# 1-Schematic_task10_1_PCB.net
KiCad netlist of a schematic drawn in EasyEDA
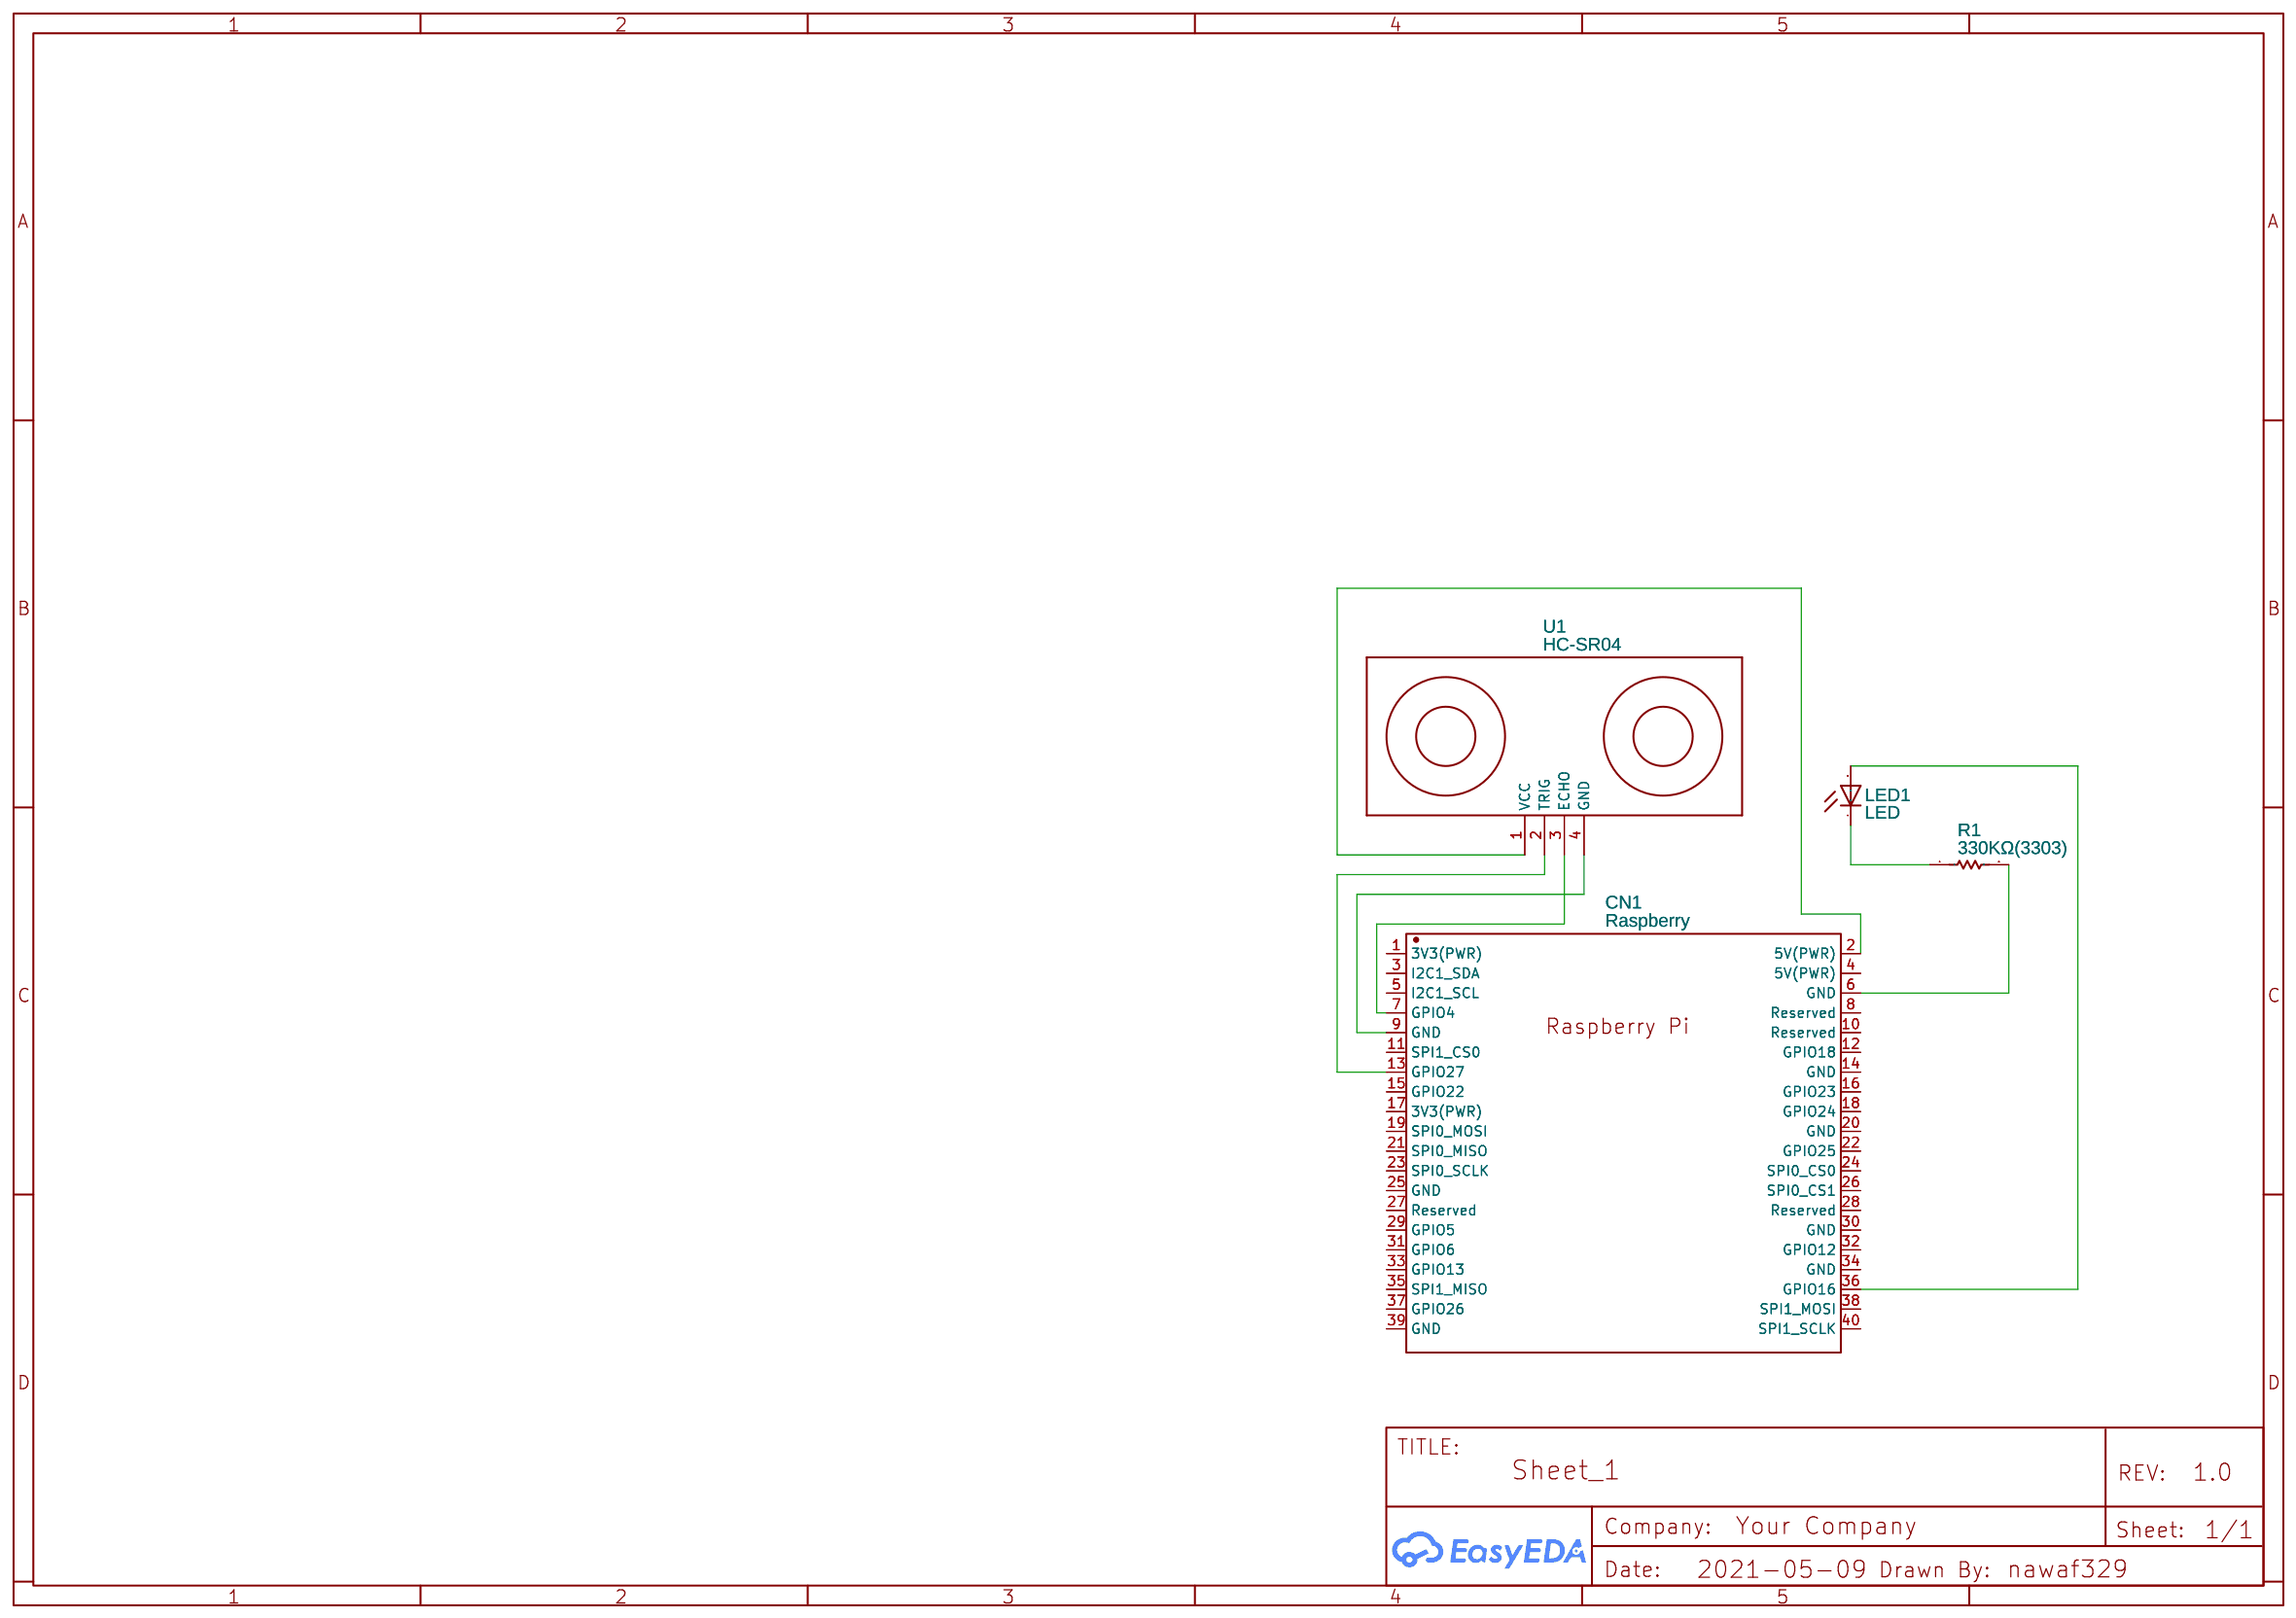
[diagram p0: schematic sheet]

(export (version "E")
  (design (tool "Eeschema 10.0.6"))
  (components
    (comp (ref "CN1") (value "Raspberry") (libsource (lib "") (part "Raspberry Pi 2")))
    (comp (ref "LED1") (value "LED") (libsource (lib "") (part "LED")))
    (comp (ref "R1")
      (value "330KΩ(3303)")
      (fields (field (name "BOM_Manufacturer Part") "RALEC") (field (name "BOM_Supplier Part") "undefined"))
      (libsource (lib "") (part "330KΩ(3303)"))
    )
    (comp (ref "U1") (value "HC-SR04") (libsource (lib "") (part "HC-SR04")))
  )
  (nets
    (net (code "1") (name "Net-(CN1-GND-Pad6)") (class "Default")
      (node (ref "CN1") (pin "6") (pinfunction "GND_6") (pintype "passive"))
      (node (ref "R1") (pin "2") (pinfunction "2_2") (pintype "unspecified"))
    )
    (net (code "2") (name "Net-(CN1-GPIO4)") (class "Default")
      (node (ref "CN1") (pin "7") (pinfunction "GPIO4_7") (pintype "bidirectional"))
      (node (ref "U1") (pin "3") (pinfunction "ECHO_3") (pintype "output"))
    )
    (net (code "3") (name "Net-(CN1-GPIO16)") (class "Default")
      (node (ref "CN1") (pin "36") (pinfunction "GPIO16_36") (pintype "bidirectional"))
      (node (ref "LED1") (pin "A") (pinfunction "A_A") (pintype "unspecified"))
    )
    (net (code "4") (name "Net-(CN1-GPIO27)") (class "Default")
      (node (ref "CN1") (pin "13") (pinfunction "GPIO27_13") (pintype "bidirectional"))
      (node (ref "U1") (pin "2") (pinfunction "TRIG_2") (pintype "input"))
    )
    (net (code "5") (name "Net-(LED1-C)") (class "Default")
      (node (ref "LED1") (pin "K") (pinfunction "C_K") (pintype "unspecified"))
      (node (ref "R1") (pin "1") (pinfunction "1_1") (pintype "unspecified"))
    )
    (net (code "6") (name "Net-(U1-GND)") (class "Default")
      (node (ref "CN1") (pin "9") (pinfunction "GND_9") (pintype "passive"))
      (node (ref "U1") (pin "4") (pinfunction "GND_4") (pintype "passive"))
    )
    (net (code "7") (name "Net-(U1-VCC)") (class "Default")
      (node (ref "CN1") (pin "2") (pinfunction "5V(PWR)_2") (pintype "passive"))
      (node (ref "U1") (pin "1") (pinfunction "VCC_1") (pintype "passive"))
    )
    (net (code "8") (name "unconnected-(CN1-3V3(PWR)-Pad1)") (class "Default")
      (node (ref "CN1") (pin "1") (pinfunction "3V3(PWR)_1") (pintype "passive"))
    )
    (net (code "9") (name "unconnected-(CN1-3V3(PWR)-Pad17)") (class "Default")
      (node (ref "CN1") (pin "17") (pinfunction "3V3(PWR)_17") (pintype "passive"))
    )
    (net (code "10") (name "unconnected-(CN1-5V(PWR)-Pad4)") (class "Default")
      (node (ref "CN1") (pin "4") (pinfunction "5V(PWR)_4") (pintype "passive"))
    )
    (net (code "11") (name "unconnected-(CN1-GND-Pad14)") (class "Default")
      (node (ref "CN1") (pin "14") (pinfunction "GND_14") (pintype "passive"))
    )
    (net (code "12") (name "unconnected-(CN1-GND-Pad20)") (class "Default")
      (node (ref "CN1") (pin "20") (pinfunction "GND_20") (pintype "passive"))
    )
    (net (code "13") (name "unconnected-(CN1-GND-Pad25)") (class "Default")
      (node (ref "CN1") (pin "25") (pinfunction "GND_25") (pintype "passive"))
    )
    (net (code "14") (name "unconnected-(CN1-GND-Pad30)") (class "Default")
      (node (ref "CN1") (pin "30") (pinfunction "GND_30") (pintype "passive"))
    )
    (net (code "15") (name "unconnected-(CN1-GND-Pad34)") (class "Default")
      (node (ref "CN1") (pin "34") (pinfunction "GND_34") (pintype "passive"))
    )
    (net (code "16") (name "unconnected-(CN1-GND-Pad39)") (class "Default")
      (node (ref "CN1") (pin "39") (pinfunction "GND_39") (pintype "passive"))
    )
    (net (code "17") (name "unconnected-(CN1-GPIO5-Pad29)") (class "Default")
      (node (ref "CN1") (pin "29") (pinfunction "GPIO5_29") (pintype "bidirectional"))
    )
    (net (code "18") (name "unconnected-(CN1-GPIO6-Pad31)") (class "Default")
      (node (ref "CN1") (pin "31") (pinfunction "GPIO6_31") (pintype "bidirectional"))
    )
    (net (code "19") (name "unconnected-(CN1-GPIO12-Pad32)") (class "Default")
      (node (ref "CN1") (pin "32") (pinfunction "GPIO12_32") (pintype "bidirectional"))
    )
    (net (code "20") (name "unconnected-(CN1-GPIO13-Pad33)") (class "Default")
      (node (ref "CN1") (pin "33") (pinfunction "GPIO13_33") (pintype "bidirectional"))
    )
    (net (code "21") (name "unconnected-(CN1-GPIO18-Pad12)") (class "Default")
      (node (ref "CN1") (pin "12") (pinfunction "GPIO18_12") (pintype "bidirectional"))
    )
    (net (code "22") (name "unconnected-(CN1-GPIO22-Pad15)") (class "Default")
      (node (ref "CN1") (pin "15") (pinfunction "GPIO22_15") (pintype "output"))
    )
    (net (code "23") (name "unconnected-(CN1-GPIO23-Pad16)") (class "Default")
      (node (ref "CN1") (pin "16") (pinfunction "GPIO23_16") (pintype "bidirectional"))
    )
    (net (code "24") (name "unconnected-(CN1-GPIO24-Pad18)") (class "Default")
      (node (ref "CN1") (pin "18") (pinfunction "GPIO24_18") (pintype "bidirectional"))
    )
    (net (code "25") (name "unconnected-(CN1-GPIO25-Pad22)") (class "Default")
      (node (ref "CN1") (pin "22") (pinfunction "GPIO25_22") (pintype "bidirectional"))
    )
    (net (code "26") (name "unconnected-(CN1-GPIO26-Pad37)") (class "Default")
      (node (ref "CN1") (pin "37") (pinfunction "GPIO26_37") (pintype "bidirectional"))
    )
    (net (code "27") (name "unconnected-(CN1-I2C1_SCL-Pad5)") (class "Default")
      (node (ref "CN1") (pin "5") (pinfunction "I2C1_SCL_5") (pintype "bidirectional"))
    )
    (net (code "28") (name "unconnected-(CN1-I2C1_SDA-Pad3)") (class "Default")
      (node (ref "CN1") (pin "3") (pinfunction "I2C1_SDA_3") (pintype "bidirectional"))
    )
    (net (code "29") (name "unconnected-(CN1-Reserved-Pad8)") (class "Default")
      (node (ref "CN1") (pin "8") (pinfunction "Reserved_8") (pintype "passive"))
    )
    (net (code "30") (name "unconnected-(CN1-Reserved-Pad10)") (class "Default")
      (node (ref "CN1") (pin "10") (pinfunction "Reserved_10") (pintype "bidirectional"))
    )
    (net (code "31") (name "unconnected-(CN1-Reserved-Pad27)") (class "Default")
      (node (ref "CN1") (pin "27") (pinfunction "Reserved_27") (pintype "unspecified"))
    )
    (net (code "32") (name "unconnected-(CN1-Reserved-Pad28)") (class "Default")
      (node (ref "CN1") (pin "28") (pinfunction "Reserved_28") (pintype "unspecified"))
    )
    (net (code "33") (name "unconnected-(CN1-SPI0_CS0-Pad24)") (class "Default")
      (node (ref "CN1") (pin "24") (pinfunction "SPI0_CS0_24") (pintype "bidirectional"))
    )
    (net (code "34") (name "unconnected-(CN1-SPI0_CS1-Pad26)") (class "Default")
      (node (ref "CN1") (pin "26") (pinfunction "SPI0_CS1_26") (pintype "bidirectional"))
    )
    (net (code "35") (name "unconnected-(CN1-SPI0_MISO-Pad21)") (class "Default")
      (node (ref "CN1") (pin "21") (pinfunction "SPI0_MISO_21") (pintype "bidirectional"))
    )
    (net (code "36") (name "unconnected-(CN1-SPI0_MOSI-Pad19)") (class "Default")
      (node (ref "CN1") (pin "19") (pinfunction "SPI0_MOSI_19") (pintype "bidirectional"))
    )
    (net (code "37") (name "unconnected-(CN1-SPI0_SCLK-Pad23)") (class "Default")
      (node (ref "CN1") (pin "23") (pinfunction "SPI0_SCLK_23") (pintype "bidirectional"))
    )
    (net (code "38") (name "unconnected-(CN1-SPI1_CS0-Pad11)") (class "Default")
      (node (ref "CN1") (pin "11") (pinfunction "SPI1_CS0_11") (pintype "bidirectional"))
    )
    (net (code "39") (name "unconnected-(CN1-SPI1_MISO-Pad35)") (class "Default")
      (node (ref "CN1") (pin "35") (pinfunction "SPI1_MISO_35") (pintype "bidirectional"))
    )
    (net (code "40") (name "unconnected-(CN1-SPI1_MOSI-Pad38)") (class "Default")
      (node (ref "CN1") (pin "38") (pinfunction "SPI1_MOSI_38") (pintype "bidirectional"))
    )
    (net (code "41") (name "unconnected-(CN1-SPI1_SCLK-Pad40)") (class "Default")
      (node (ref "CN1") (pin "40") (pinfunction "SPI1_SCLK_40") (pintype "bidirectional"))
    )
  )
)
